# schematic.net
KiCad netlist of a schematic drawn in EAGLE
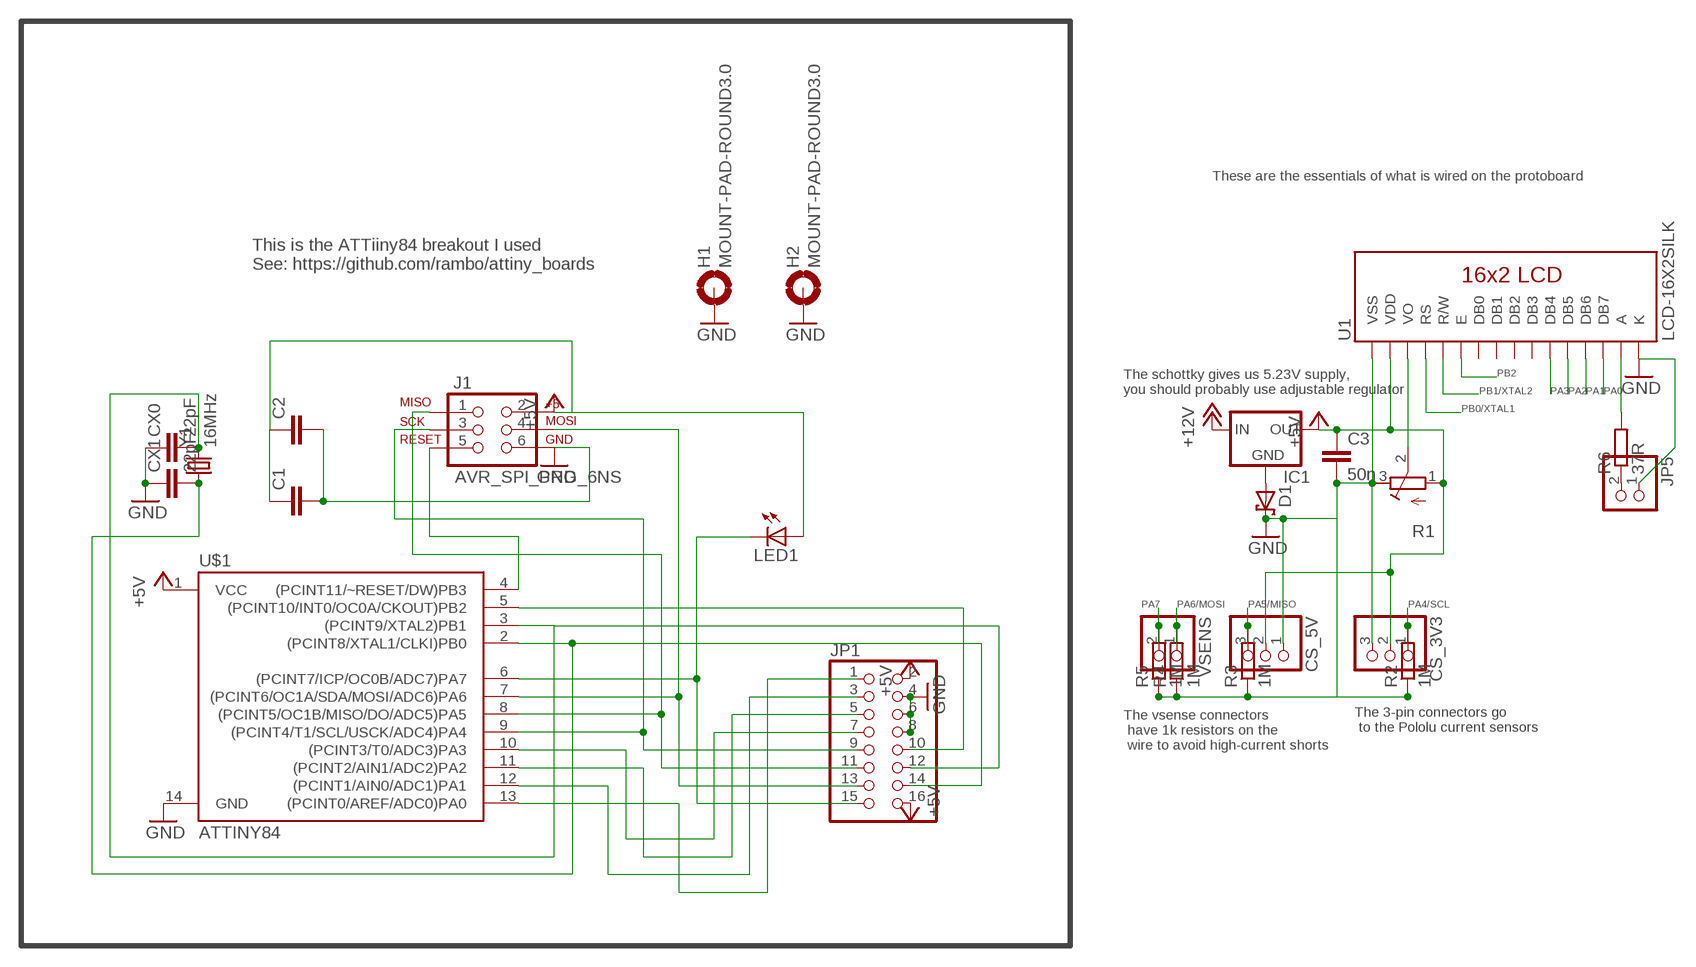
[diagram p0: schematic, sheet 1]

(export (version "E")
  (design (tool "Eeschema 10.0.6"))
  (components
    (comp (ref "C1")
      (value "C-EUC0805")
      (footprint "eagle-import:C0805")
      (libsource (lib "eagle-import") (part "C-EUC0805"))
    )
    (comp (ref "C2")
      (value "C-EUC0805")
      (footprint "eagle-import:C0805")
      (libsource (lib "eagle-import") (part "C-EUC0805"))
    )
    (comp (ref "C3")
      (value "50n")
      (footprint "eagle-import:C025-025X050")
      (libsource (lib "eagle-import") (part "C-EU025-025X050"))
    )
    (comp (ref "CS_3V3")
      (value "PINHD-1X3")
      (footprint "eagle-import:1X03")
      (libsource (lib "eagle-import") (part "PINHD-1X3"))
    )
    (comp (ref "CS_5V")
      (value "PINHD-1X3")
      (footprint "eagle-import:1X03")
      (libsource (lib "eagle-import") (part "PINHD-1X3"))
    )
    (comp (ref "CX0")
      (value "22pF")
      (footprint "eagle-import:C0603")
      (libsource (lib "eagle-import") (part "C-EUC0603"))
    )
    (comp (ref "CX1")
      (value "22pF")
      (footprint "eagle-import:C0603")
      (libsource (lib "eagle-import") (part "C-EUC0603"))
    )
    (comp (ref "D1")
      (value "SCHOTTKY-DIODEC4111-15")
      (footprint "eagle-import:C4111-15")
      (libsource (lib "eagle-import") (part "SCHOTTKY-DIODEC4111-15"))
    )
    (comp (ref "H1")
      (value "MOUNT-PAD-ROUND3.0")
      (footprint "eagle-import:3,0-PAD")
      (libsource (lib "eagle-import") (part "MOUNT-PAD-ROUND3.0"))
    )
    (comp (ref "H2")
      (value "MOUNT-PAD-ROUND3.0")
      (footprint "eagle-import:3,0-PAD")
      (libsource (lib "eagle-import") (part "MOUNT-PAD-ROUND3.0"))
    )
    (comp (ref "IC1")
      (value "V_REG_78XX-TO-220")
      (footprint "eagle-import:TO-220-ALT")
      (libsource (lib "eagle-import") (part "V_REG_78XX-TO-220"))
    )
    (comp (ref "J1")
      (value "AVR_SPI_PRG_6NS")
      (footprint "eagle-import:2X3-NS")
      (libsource (lib "eagle-import") (part "AVR_SPI_PRG_6NS"))
    )
    (comp (ref "JP1")
      (value "PINHD-2X8")
      (footprint "eagle-import:2X08")
      (libsource (lib "eagle-import") (part "PINHD-2X8"))
    )
    (comp (ref "JP5")
      (value "PINHD-1X2")
      (footprint "eagle-import:1X02")
      (libsource (lib "eagle-import") (part "PINHD-1X2"))
    )
    (comp (ref "LED1")
      (value "LED0603")
      (footprint "eagle-import:LED-0603")
      (libsource (lib "eagle-import") (part "LED0603"))
    )
    (comp (ref "R1")
      (value "R-TRIMM64W")
      (footprint "eagle-import:RTRIM64W")
      (libsource (lib "eagle-import") (part "R-TRIMM64W"))
    )
    (comp (ref "R2")
      (value "1M")
      (footprint "eagle-import:0204_7")
      (libsource (lib "eagle-import") (part "R-EU_0204/7"))
    )
    (comp (ref "R3")
      (value "1M")
      (footprint "eagle-import:0204_7")
      (libsource (lib "eagle-import") (part "R-EU_0204/7"))
    )
    (comp (ref "R4")
      (value "1M")
      (footprint "eagle-import:0204_7")
      (libsource (lib "eagle-import") (part "R-EU_0204/7"))
    )
    (comp (ref "R5")
      (value "1M")
      (footprint "eagle-import:0204_7")
      (libsource (lib "eagle-import") (part "R-EU_0204/7"))
    )
    (comp (ref "R6")
      (value "37R")
      (footprint "eagle-import:0204_7")
      (libsource (lib "eagle-import") (part "R-EU_0204/7"))
    )
    (comp (ref "U$1")
      (value "ATTINY84")
      (footprint "eagle-import:SO14")
      (libsource (lib "eagle-import") (part "ATTINY84"))
    )
    (comp (ref "U1")
      (value "LCD-16X2SILK")
      (footprint "eagle-import:LCD-16X2")
      (libsource (lib "eagle-import") (part "LCD-16X2SILK"))
    )
    (comp (ref "VSENS")
      (value "PINHD-1X2")
      (footprint "eagle-import:1X02")
      (libsource (lib "eagle-import") (part "PINHD-1X2"))
    )
    (comp (ref "Y1")
      (value "16MHz")
      (footprint "eagle-import:CRYSTAL-SMD-5X3")
      (libsource (lib "eagle-import") (part "CRYSTAL5X3"))
    )
  )
  (nets
    (net (code "1") (name "+5V") (class "Default")
      (node (ref "C1") (pin "1") (pinfunction "1_1") (pintype "passive"))
      (node (ref "C2") (pin "1") (pinfunction "1_1") (pintype "passive"))
      (node (ref "C3") (pin "1") (pinfunction "1_1") (pintype "passive"))
      (node (ref "CS_3V3") (pin "2") (pinfunction "2_2") (pintype "passive"))
      (node (ref "CS_5V") (pin "2") (pinfunction "2_2") (pintype "passive"))
      (node (ref "IC1") (pin "OUT") (pinfunction "OUT_OUT") (pintype "output"))
      (node (ref "J1") (pin "2") (pinfunction "2_2") (pintype "passive"))
      (node (ref "JP1") (pin "16") (pinfunction "16_16") (pintype "passive"))
      (node (ref "JP1") (pin "2") (pinfunction "2_2") (pintype "passive"))
      (node (ref "LED1") (pin "A") (pinfunction "A_A") (pintype "passive"))
      (node (ref "R1") (pin "1") (pinfunction "A_1") (pintype "passive"))
      (node (ref "U$1") (pin "1") (pinfunction "VCC_1") (pintype "bidirectional"))
      (node (ref "U1") (pin "2") (pinfunction "VDD_2") (pintype "power_in"))
    )
    (net (code "2") (name "+12V") (class "Default")
      (node (ref "IC1") (pin "IN") (pinfunction "IN_IN") (pintype "input"))
    )
    (net (code "3") (name "/PA0") (class "Default")
      (node (ref "JP1") (pin "1") (pinfunction "1_1") (pintype "passive"))
      (node (ref "U$1") (pin "13") (pinfunction "(PCINT0/AREF/ADC0)PA0_13") (pintype "bidirectional"))
      (node (ref "U1") (pin "14") (pinfunction "DB7_14") (pintype "bidirectional"))
    )
    (net (code "4") (name "/PA1") (class "Default")
      (node (ref "JP1") (pin "3") (pinfunction "3_3") (pintype "passive"))
      (node (ref "U$1") (pin "12") (pinfunction "(PCINT1/AIN0/ADC1)PA1_12") (pintype "bidirectional"))
      (node (ref "U1") (pin "13") (pinfunction "DB6_13") (pintype "bidirectional"))
    )
    (net (code "5") (name "/PA2") (class "Default")
      (node (ref "JP1") (pin "5") (pinfunction "5_5") (pintype "passive"))
      (node (ref "U$1") (pin "11") (pinfunction "(PCINT2/AIN1/ADC2)PA2_11") (pintype "bidirectional"))
      (node (ref "U1") (pin "12") (pinfunction "DB5_12") (pintype "bidirectional"))
    )
    (net (code "6") (name "/PA3") (class "Default")
      (node (ref "JP1") (pin "7") (pinfunction "7_7") (pintype "passive"))
      (node (ref "U$1") (pin "10") (pinfunction "(PCINT3/T0/ADC3)PA3_10") (pintype "bidirectional"))
      (node (ref "U1") (pin "11") (pinfunction "DB4_11") (pintype "bidirectional"))
    )
    (net (code "7") (name "/PA4{slash}SCL") (class "Default")
      (node (ref "CS_3V3") (pin "1") (pinfunction "1_1") (pintype "passive"))
      (node (ref "J1") (pin "3") (pinfunction "3_3") (pintype "passive"))
      (node (ref "JP1") (pin "9") (pinfunction "9_9") (pintype "passive"))
      (node (ref "R2") (pin "2") (pinfunction "2_2") (pintype "passive"))
      (node (ref "U$1") (pin "9") (pinfunction "(PCINT4/T1/SCL/USCK/ADC4)PA4_9") (pintype "bidirectional"))
    )
    (net (code "8") (name "/PA5{slash}MISO") (class "Default")
      (node (ref "CS_5V") (pin "3") (pinfunction "3_3") (pintype "passive"))
      (node (ref "J1") (pin "1") (pinfunction "1_1") (pintype "passive"))
      (node (ref "JP1") (pin "11") (pinfunction "11_11") (pintype "passive"))
      (node (ref "R3") (pin "2") (pinfunction "2_2") (pintype "passive"))
      (node (ref "U$1") (pin "8") (pinfunction "(PCINT5/OC1B/MISO/DO/ADC5)PA5_8") (pintype "bidirectional"))
    )
    (net (code "9") (name "/PA6{slash}MOSI") (class "Default")
      (node (ref "J1") (pin "4") (pinfunction "4_4") (pintype "passive"))
      (node (ref "JP1") (pin "13") (pinfunction "13_13") (pintype "passive"))
      (node (ref "R4") (pin "2") (pinfunction "2_2") (pintype "passive"))
      (node (ref "U$1") (pin "7") (pinfunction "(PCINT6/OC1A/SDA/MOSI/ADC6)PA6_7") (pintype "bidirectional"))
      (node (ref "VSENS") (pin "1") (pinfunction "1_1") (pintype "passive"))
    )
    (net (code "10") (name "/PA7") (class "Default")
      (node (ref "JP1") (pin "15") (pinfunction "15_15") (pintype "passive"))
      (node (ref "LED1") (pin "C") (pinfunction "C_C") (pintype "passive"))
      (node (ref "R5") (pin "2") (pinfunction "2_2") (pintype "passive"))
      (node (ref "U$1") (pin "6") (pinfunction "(PCINT7/ICP/OC0B/ADC7)PA7_6") (pintype "bidirectional"))
      (node (ref "VSENS") (pin "2") (pinfunction "2_2") (pintype "passive"))
    )
    (net (code "11") (name "/PB0{slash}XTAL1") (class "Default")
      (node (ref "CX1") (pin "2") (pinfunction "2_2") (pintype "passive"))
      (node (ref "JP1") (pin "14") (pinfunction "14_14") (pintype "passive"))
      (node (ref "U$1") (pin "2") (pinfunction "(PCINT8/XTAL1/CLKI)PB0_2") (pintype "bidirectional"))
      (node (ref "U1") (pin "4") (pinfunction "RS_4") (pintype "input"))
      (node (ref "Y1") (pin "1") (pinfunction "1_1") (pintype "passive"))
    )
    (net (code "12") (name "/PB1{slash}XTAL2") (class "Default")
      (node (ref "CX0") (pin "2") (pinfunction "2_2") (pintype "passive"))
      (node (ref "JP1") (pin "12") (pinfunction "12_12") (pintype "passive"))
      (node (ref "U$1") (pin "3") (pinfunction "(PCINT9/XTAL2)PB1_3") (pintype "bidirectional"))
      (node (ref "U1") (pin "5") (pinfunction "R/W_5") (pintype "input"))
      (node (ref "Y1") (pin "3") (pinfunction "2_3") (pintype "passive"))
    )
    (net (code "13") (name "/PB2") (class "Default")
      (node (ref "JP1") (pin "10") (pinfunction "10_10") (pintype "passive"))
      (node (ref "U$1") (pin "5") (pinfunction "(PCINT10/INT0/OC0A/CKOUT)PB2_5") (pintype "bidirectional"))
      (node (ref "U1") (pin "6") (pinfunction "E_6") (pintype "input"))
    )
    (net (code "14") (name "GND") (class "Default")
      (node (ref "C1") (pin "2") (pinfunction "2_2") (pintype "passive"))
      (node (ref "C2") (pin "2") (pinfunction "2_2") (pintype "passive"))
      (node (ref "C3") (pin "2") (pinfunction "2_2") (pintype "passive"))
      (node (ref "CS_3V3") (pin "3") (pinfunction "3_3") (pintype "passive"))
      (node (ref "CS_5V") (pin "1") (pinfunction "1_1") (pintype "passive"))
      (node (ref "CX0") (pin "1") (pinfunction "1_1") (pintype "passive"))
      (node (ref "CX1") (pin "1") (pinfunction "1_1") (pintype "passive"))
      (node (ref "D1") (pin "C") (pinfunction "C_C") (pintype "passive"))
      (node (ref "H1") (pin "B3,0") (pinfunction "MOUNT_B3,0") (pintype "passive"))
      (node (ref "H2") (pin "B3,0") (pinfunction "MOUNT_B3,0") (pintype "passive"))
      (node (ref "J1") (pin "6") (pinfunction "6_6") (pintype "passive"))
      (node (ref "JP1") (pin "4") (pinfunction "4_4") (pintype "passive"))
      (node (ref "JP1") (pin "6") (pinfunction "6_6") (pintype "passive"))
      (node (ref "JP1") (pin "8") (pinfunction "8_8") (pintype "passive"))
      (node (ref "JP5") (pin "1") (pinfunction "1_1") (pintype "passive"))
      (node (ref "R1") (pin "3") (pinfunction "E_3") (pintype "passive"))
      (node (ref "R2") (pin "1") (pinfunction "1_1") (pintype "passive"))
      (node (ref "R3") (pin "1") (pinfunction "1_1") (pintype "passive"))
      (node (ref "R4") (pin "1") (pinfunction "1_1") (pintype "passive"))
      (node (ref "R5") (pin "1") (pinfunction "1_1") (pintype "passive"))
      (node (ref "U$1") (pin "14") (pinfunction "GND_14") (pintype "bidirectional"))
      (node (ref "U1") (pin "1") (pinfunction "VSS_1") (pintype "power_in"))
      (node (ref "U1") (pin "16") (pinfunction "K_16") (pintype "power_in"))
    )
    (net (code "15") (name "Net-(D1-PadA)") (class "Default")
      (node (ref "D1") (pin "A") (pinfunction "A_A") (pintype "passive"))
      (node (ref "IC1") (pin "GND") (pinfunction "GND_GND") (pintype "input"))
    )
    (net (code "16") (name "Net-(JP5-Pad2)") (class "Default")
      (node (ref "JP5") (pin "2") (pinfunction "2_2") (pintype "passive"))
      (node (ref "R6") (pin "1") (pinfunction "1_1") (pintype "passive"))
    )
    (net (code "17") (name "Net-(R1-S)") (class "Default")
      (node (ref "R1") (pin "2") (pinfunction "S_2") (pintype "passive"))
      (node (ref "U1") (pin "3") (pinfunction "VO_3") (pintype "bidirectional"))
    )
    (net (code "18") (name "Net-(U$1-(PCINT11{slash}~{RESET{slash}DW})PB3)") (class "Default")
      (node (ref "J1") (pin "5") (pinfunction "5_5") (pintype "passive"))
      (node (ref "U$1") (pin "4") (pinfunction "(PCINT11/~{RESET/DW})PB3_4") (pintype "bidirectional"))
    )
    (net (code "19") (name "Net-(U1-A)") (class "Default")
      (node (ref "R6") (pin "2") (pinfunction "2_2") (pintype "passive"))
      (node (ref "U1") (pin "15") (pinfunction "A_15") (pintype "power_in"))
    )
    (net (code "20") (name "unconnected-(U1-DB0-Pad7)") (class "Default")
      (node (ref "U1") (pin "7") (pinfunction "DB0_7") (pintype "bidirectional"))
    )
    (net (code "21") (name "unconnected-(U1-DB1-Pad8)") (class "Default")
      (node (ref "U1") (pin "8") (pinfunction "DB1_8") (pintype "bidirectional"))
    )
    (net (code "22") (name "unconnected-(U1-DB2-Pad9)") (class "Default")
      (node (ref "U1") (pin "9") (pinfunction "DB2_9") (pintype "bidirectional"))
    )
    (net (code "23") (name "unconnected-(U1-DB3-Pad10)") (class "Default")
      (node (ref "U1") (pin "10") (pinfunction "DB3_10") (pintype "bidirectional"))
    )
  )
)
